# RS232.net
KiCad netlist of a schematic drawn in Altium Designer
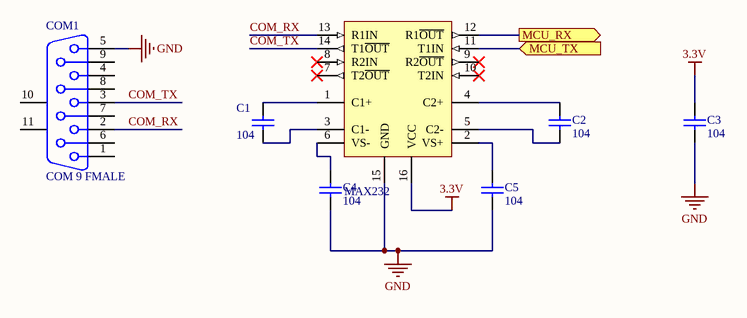
[diagram p0: RS232.SchDoc]

(export (version "E")
  (design (tool "Eeschema 10.0.6"))
  (components
    (comp (ref "C1")
      (value "104")
      (footprint "tu 0805")
      (description "Dán")
      (libsource (lib "Altium_Lib_by_KhueNguyenCreator") (part "Tu 0805 104 50V 10%"))
    )
    (comp (ref "C2")
      (value "104")
      (footprint "tu 0805")
      (description "Dán")
      (libsource (lib "Altium_Lib_by_KhueNguyenCreator") (part "Tu 0805 104 50V 10%"))
    )
    (comp (ref "C3")
      (value "104")
      (footprint "tu 0805")
      (description "Dán")
      (libsource (lib "Altium_Lib_by_KhueNguyenCreator") (part "Tu 0805 104 50V 10%"))
    )
    (comp (ref "C4")
      (value "104")
      (footprint "tu 0805")
      (description "Dán")
      (libsource (lib "Altium_Lib_by_KhueNguyenCreator") (part "Tu 0805 104 50V 10%"))
    )
    (comp (ref "C5")
      (value "104")
      (footprint "tu 0805")
      (description "Dán")
      (libsource (lib "Altium_Lib_by_KhueNguyenCreator") (part "Tu 0805 104 50V 10%"))
    )
    (comp (ref "COM1")
      (value "COM 9 FMALE")
      (footprint "DSB 9-F")
      (description "COM 9")
      (fields (field (name "PUBLISHER") "Altium Limited"))
      (libsource (lib "syhaunguyen") (part "DSB9F"))
    )
    (comp (ref "IC1")
      (value "MAX232")
      (footprint "DIP16/W0.3")
      (description "Dual EIA-232 Driver/Receiver")
      (libsource (lib "My library altium") (part "MAX232"))
    )
  )
  (nets
    (net (code "1") (name "/COM_RX") (class "Default")
      (node (ref "COM1") (pin "2") (pinfunction "2_2") (pintype "passive"))
      (node (ref "IC1") (pin "13") (pinfunction "R1IN_13") (pintype "input"))
    )
    (net (code "2") (name "/COM_TX") (class "Default")
      (node (ref "COM1") (pin "3") (pinfunction "3_3") (pintype "passive"))
      (node (ref "IC1") (pin "14") (pinfunction "T1~{OUT}_14") (pintype "output"))
    )
    (net (code "3") (name "/MCU_RX") (class "Default")
      (node (ref "IC1") (pin "12") (pinfunction "R1~{OUT}_12") (pintype "output"))
    )
    (net (code "4") (name "/MCU_TX") (class "Default")
      (node (ref "IC1") (pin "11") (pinfunction "T1IN_11") (pintype "input"))
    )
    (net (code "5") (name "3.3V") (class "Default")
      (node (ref "C3") (pin "1") (pinfunction "1_1") (pintype "passive"))
      (node (ref "IC1") (pin "16") (pinfunction "VCC_16") (pintype "power_in"))
    )
    (net (code "6") (name "GND") (class "Default")
      (node (ref "C3") (pin "2") (pinfunction "2_2") (pintype "passive"))
      (node (ref "C4") (pin "2") (pinfunction "2_2") (pintype "passive"))
      (node (ref "C5") (pin "2") (pinfunction "2_2") (pintype "passive"))
      (node (ref "COM1") (pin "5") (pinfunction "5_5") (pintype "passive"))
      (node (ref "IC1") (pin "15") (pinfunction "GND_15") (pintype "power_in"))
    )
    (net (code "7") (name "Net-(IC1-C1+)") (class "Default")
      (node (ref "C1") (pin "1") (pinfunction "1_1") (pintype "passive"))
      (node (ref "IC1") (pin "1") (pinfunction "C1+_1") (pintype "passive"))
    )
    (net (code "8") (name "Net-(IC1-C1-)") (class "Default")
      (node (ref "C1") (pin "2") (pinfunction "2_2") (pintype "passive"))
      (node (ref "IC1") (pin "3") (pinfunction "C1-_3") (pintype "passive"))
    )
    (net (code "9") (name "Net-(IC1-C2+)") (class "Default")
      (node (ref "C2") (pin "1") (pinfunction "1_1") (pintype "passive"))
      (node (ref "IC1") (pin "4") (pinfunction "C2+_4") (pintype "passive"))
    )
    (net (code "10") (name "Net-(IC1-C2-)") (class "Default")
      (node (ref "C2") (pin "2") (pinfunction "2_2") (pintype "passive"))
      (node (ref "IC1") (pin "5") (pinfunction "C2-_5") (pintype "passive"))
    )
    (net (code "11") (name "Net-(IC1-VS+)") (class "Default")
      (node (ref "C5") (pin "1") (pinfunction "1_1") (pintype "passive"))
      (node (ref "IC1") (pin "2") (pinfunction "VS+_2") (pintype "power_in"))
    )
    (net (code "12") (name "Net-(IC1-VS-)") (class "Default")
      (node (ref "C4") (pin "1") (pinfunction "1_1") (pintype "passive"))
      (node (ref "IC1") (pin "6") (pinfunction "VS-_6") (pintype "power_in"))
    )
    (net (code "13") (name "unconnected-(COM1-MH1-Pad10)") (class "Default")
      (node (ref "COM1") (pin "10") (pinfunction "MH1_10") (pintype "passive"))
    )
    (net (code "14") (name "unconnected-(COM1-MH2-Pad11)") (class "Default")
      (node (ref "COM1") (pin "11") (pinfunction "MH2_11") (pintype "passive"))
    )
    (net (code "15") (name "unconnected-(COM1-Pad1)") (class "Default")
      (node (ref "COM1") (pin "1") (pinfunction "1_1") (pintype "passive"))
    )
    (net (code "16") (name "unconnected-(COM1-Pad4)") (class "Default")
      (node (ref "COM1") (pin "4") (pinfunction "4_4") (pintype "passive"))
    )
    (net (code "17") (name "unconnected-(COM1-Pad6)") (class "Default")
      (node (ref "COM1") (pin "6") (pinfunction "6_6") (pintype "passive"))
    )
    (net (code "18") (name "unconnected-(COM1-Pad7)") (class "Default")
      (node (ref "COM1") (pin "7") (pinfunction "7_7") (pintype "passive"))
    )
    (net (code "19") (name "unconnected-(COM1-Pad8)") (class "Default")
      (node (ref "COM1") (pin "8") (pinfunction "8_8") (pintype "passive"))
    )
    (net (code "20") (name "unconnected-(COM1-Pad9)") (class "Default")
      (node (ref "COM1") (pin "9") (pinfunction "9_9") (pintype "passive"))
    )
    (net (code "21") (name "unconnected-(IC1-R2IN-Pad8)") (class "Default")
      (node (ref "IC1") (pin "8") (pinfunction "R2IN_8") (pintype "input+no_connect"))
    )
    (net (code "22") (name "unconnected-(IC1-R2~{OUT}-Pad9)") (class "Default")
      (node (ref "IC1") (pin "9") (pinfunction "R2~{OUT}_9") (pintype "output+no_connect"))
    )
    (net (code "23") (name "unconnected-(IC1-T2IN-Pad10)") (class "Default")
      (node (ref "IC1") (pin "10") (pinfunction "T2IN_10") (pintype "input+no_connect"))
    )
    (net (code "24") (name "unconnected-(IC1-T2~{OUT}-Pad7)") (class "Default")
      (node (ref "IC1") (pin "7") (pinfunction "T2~{OUT}_7") (pintype "output+no_connect"))
    )
  )
)
